# 780-00012-P4_rev4_Sch_M2_Focus_Drive.net
KiCad netlist of a schematic drawn in Altium Designer
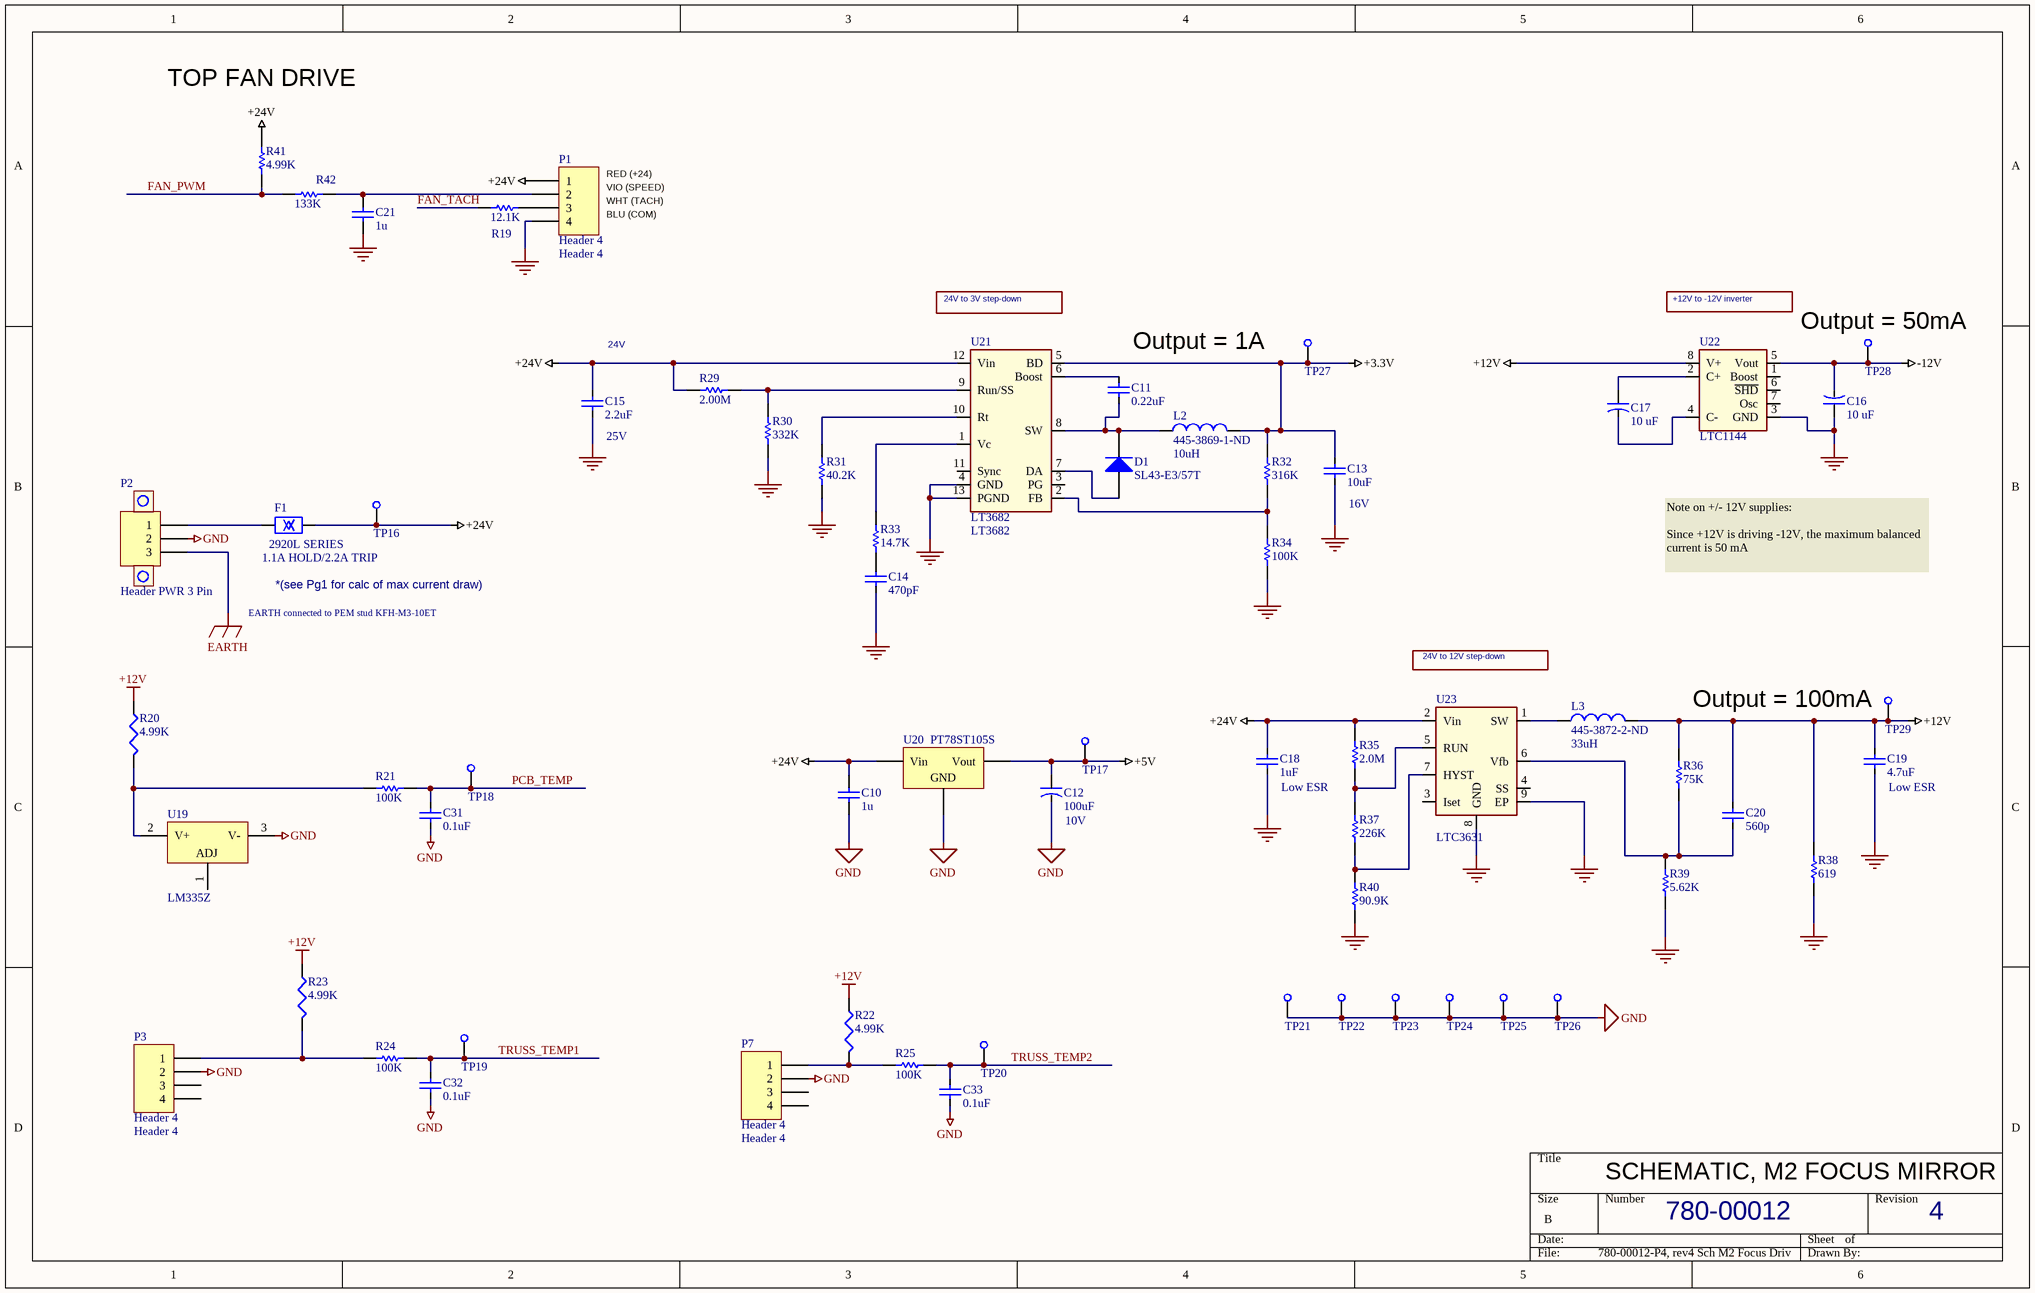
[diagram p0: 780-00012-P4, rev4 Sch M2 Focus Drive.SchDoc]

(export (version "E")
  (design (tool "Eeschema 10.0.6"))
  (components
    (comp (ref "C10")
      (value "1u")
      (footprint "2012[0805]")
      (description "Capacitor")
      (fields (field (name "MANUFACTURER") "Taiyo Yuden"))
      (libsource (lib "Miscellaneous Devices") (part "Cap"))
    )
    (comp (ref "C11")
      (value "0.22uF")
      (footprint "SMD_0805")
      (description "Capacitor")
      (fields (field (name "Comment") "Cap SMD"))
      (libsource (lib "Richs Schematic Components") (part "Cap SMD"))
    )
    (comp (ref "C12")
      (value "10V")
      (footprint "SMD_CAP_7343")
      (description "outline 6.0mm x 3.2mm")
      (fields (field (name "MANUFACTURER") "kEMET") (field (name "ALTIUM_VALUE") "100uF"))
      (libsource (lib "Richs Schematic Components") (part "Cap Tant 35V"))
    )
    (comp (ref "C13")
      (value "16V")
      (footprint "SMD_0805")
      (description "Capacitor")
      (fields (field (name "ALTIUM_VALUE") "10uF"))
      (libsource (lib "Richs Schematic Components") (part "Cap SMD"))
    )
    (comp (ref "C14")
      (value "470pF")
      (footprint "SMD_0805")
      (description "Capacitor")
      (fields (field (name "Comment") "Cap SMD"))
      (libsource (lib "Richs Schematic Components") (part "Cap SMD"))
    )
    (comp (ref "C15")
      (value "25V")
      (footprint "SMD_0805")
      (description "Capacitor")
      (fields (field (name "MANUFACTURER") "Taiyo Yuden") (field (name "ALTIUM_VALUE") "2.2uF"))
      (libsource (lib "Richs Schematic Components") (part "Cap SMD"))
    )
    (comp (ref "C16")
      (value "10 uF")
      (footprint "SMD_CAP_3216")
      (description "outline 3.2mm x 1.6mm")
      (fields (field (name "MANUFACTURER") "KEMET") (field (name "Comment") "16V"))
      (libsource (lib "Richs Schematic Components") (part "Cap Tant 16V"))
    )
    (comp (ref "C17")
      (value "10 uF")
      (footprint "SMD_CAP_3216")
      (description "outline 3.2mm x 1.6mm")
      (fields (field (name "MANUFACTURER") "KEMET") (field (name "Comment") "16V"))
      (libsource (lib "Richs Schematic Components") (part "Cap Tant 16V"))
    )
    (comp (ref "C18")
      (value "Low ESR")
      (footprint "SMD_1206")
      (description "Capacitor")
      (fields (field (name "MANUFACTURER") "TDK") (field (name "ALTIUM_VALUE") "1uF"))
      (libsource (lib "Richs Schematic Components") (part "Cap SMD"))
    )
    (comp (ref "C19")
      (value "Low ESR")
      (footprint "SMD_1206")
      (description "Capacitor")
      (fields (field (name "MANUFACTURER") "TDK") (field (name "ALTIUM_VALUE") "4.7uF"))
      (libsource (lib "Richs Schematic Components") (part "Cap SMD"))
    )
    (comp (ref "C20")
      (value "560p")
      (footprint "SMD_0805")
      (description "Capacitor")
      (fields (field (name "Comment") "Cap SMD"))
      (libsource (lib "Richs Schematic Components") (part "Cap SMD"))
    )
    (comp (ref "C21")
      (value "1u")
      (footprint "2012[0805]")
      (description "Capacitor")
      (fields (field (name "MANUFACTURER") "Taiyo Yuden"))
      (libsource (lib "Miscellaneous Devices") (part "Cap"))
    )
    (comp (ref "C31")
      (value "0.1uF")
      (footprint "SMD_0805")
      (description "Capacitor")
      (fields (field (name "MANUFACTURER") "AVX") (field (name "Comment") "Cap SMD"))
      (libsource (lib "Richs Schematic Components") (part "Cap SMD"))
    )
    (comp (ref "C32")
      (value "0.1uF")
      (footprint "SMD_0805")
      (description "Capacitor")
      (fields (field (name "MANUFACTURER") "AVX") (field (name "Comment") "Cap SMD"))
      (libsource (lib "Richs Schematic Components") (part "Cap SMD"))
    )
    (comp (ref "C33")
      (value "0.1uF")
      (footprint "SMD_0805")
      (description "Capacitor")
      (fields (field (name "MANUFACTURER") "AVX") (field (name "Comment") "Cap SMD"))
      (libsource (lib "Richs Schematic Components") (part "Cap SMD"))
    )
    (comp (ref "D1")
      (value "SL43-E3/57T")
      (footprint "DO-214AB")
      (description "Default Diode")
      (fields (field (name "MANUFACTURER") "Vishay/Dale"))
      (libsource (lib "Miscellaneous Devices") (part "Diode"))
    )
    (comp (ref "F1")
      (value "2920L SERIES")
      (footprint "SMD 2920  PolySwitch")
      (description "Polyswitch")
      (fields (field (name "ALTIUM_VALUE") "1.1A HOLD/2.2A TRIP"))
      (libsource (lib "Richs Schematic Components") (part "Fuse Resettable"))
    )
    (comp (ref "L2")
      (value "445-3869-1-ND")
      (footprint "Inductor TDC SLF")
      (description "Inductor")
      (fields (field (name "MANUFACTURER") "TDK") (field (name "ALTIUM_VALUE") "10uH"))
      (libsource (lib "Richs Schematic Components") (part "Inductor SMD 10uH 1.8A"))
    )
    (comp (ref "L3")
      (value "445-3872-2-ND")
      (footprint "Inductor TDC SLF")
      (description "Inductor")
      (fields (field (name "MANUFACTURER") "TDK") (field (name "ALTIUM_VALUE") "33uH"))
      (libsource (lib "Richs Schematic Components") (part "Inductor SMD 10uH 1.8A"))
    )
    (comp (ref "P1")
      (value "Header 4")
      (footprint "HDR1X4 for IDC")
      (description "Header, 4-Pin")
      (fields (field (name "ALTIUM_VALUE") "Header 4"))
      (libsource (lib "") (part "Header 4_1"))
    )
    (comp (ref "P2")
      (value "Header PWR 3 Pin")
      (footprint "HDR-3 pin w/screw")
      (description "Header, 3-Pin")
      (fields (field (name "MANUFACTURER") "Tyco"))
      (libsource (lib "Richs Schematic Components") (part "Header 3 PWR"))
    )
    (comp (ref "P3")
      (value "Header 4")
      (footprint "HDR1X4 for IDC")
      (description "Header, 4-Pin")
      (fields (field (name "ALTIUM_VALUE") "Header 4"))
      (libsource (lib "Richs Schematic Components") (part "Header 4"))
    )
    (comp (ref "P7")
      (value "Header 4")
      (footprint "HDR1X4 for IDC")
      (description "Header, 4-Pin")
      (fields (field (name "ALTIUM_VALUE") "Header 4"))
      (libsource (lib "Richs Schematic Components") (part "Header 4"))
    )
    (comp (ref "R19")
      (value "12.1K")
      (footprint "SMD_0805")
      (description "Resistor 0805")
      (fields (field (name "MANUFACTURER") "Vishay/Dale") (field (name "Comment") "Res 0805"))
      (libsource (lib "Richs Schematic Components") (part "Res SMD"))
    )
    (comp (ref "R20")
      (value "4.99K")
      (footprint "smd_0805")
      (description "Resistor")
      (fields (field (name "MANUFACTURER") "DALE") (field (name "Comment") "Res3"))
      (libsource (lib "Miscellaneous Devices") (part "Res3"))
    )
    (comp (ref "R21")
      (value "100K")
      (footprint "SMD_0805")
      (description "Resistor")
      (fields (field (name "MANUFACTURER") "Vishay/Dale") (field (name "Comment") "Res SMD"))
      (libsource (lib "Richs Schematic Components") (part "Res SMD"))
    )
    (comp (ref "R22")
      (value "4.99K")
      (footprint "smd_0805")
      (description "Resistor")
      (fields (field (name "MANUFACTURER") "DALE") (field (name "Comment") "Res3"))
      (libsource (lib "Miscellaneous Devices") (part "Res3"))
    )
    (comp (ref "R23")
      (value "4.99K")
      (footprint "smd_0805")
      (description "Resistor")
      (fields (field (name "MANUFACTURER") "DALE") (field (name "Comment") "Res3"))
      (libsource (lib "Miscellaneous Devices") (part "Res3"))
    )
    (comp (ref "R24")
      (value "100K")
      (footprint "SMD_0805")
      (description "Resistor")
      (fields (field (name "MANUFACTURER") "Vishay/Dale") (field (name "Comment") "Res SMD"))
      (libsource (lib "Richs Schematic Components") (part "Res SMD"))
    )
    (comp (ref "R25")
      (value "100K")
      (footprint "SMD_0805")
      (description "Resistor")
      (fields (field (name "MANUFACTURER") "Vishay/Dale") (field (name "Comment") "Res SMD"))
      (libsource (lib "Richs Schematic Components") (part "Res SMD"))
    )
    (comp (ref "R29")
      (value "2.00M")
      (footprint "SMD_0805")
      (description "Resistor 0805")
      (fields (field (name "MANUFACTURER") "Vishay/Dale") (field (name "Comment") "Res 0805"))
      (libsource (lib "Richs Schematic Components") (part "Res SMD"))
    )
    (comp (ref "R30")
      (value "332K")
      (footprint "SMD_0805")
      (description "Resistor 0805")
      (fields (field (name "MANUFACTURER") "Vishay/Dale") (field (name "Comment") "Res 0805"))
      (libsource (lib "Richs Schematic Components") (part "Res SMD"))
    )
    (comp (ref "R31")
      (value "40.2K")
      (footprint "SMD_0805")
      (description "Resistor 0805")
      (fields (field (name "MANUFACTURER") "Vishay/Dale") (field (name "Comment") "Res 0805"))
      (libsource (lib "Richs Schematic Components") (part "Res SMD"))
    )
    (comp (ref "R32")
      (value "316K")
      (footprint "SMD_0805")
      (description "Resistor 0805")
      (fields (field (name "MANUFACTURER") "Vishay/Dale") (field (name "Comment") "Res 0805"))
      (libsource (lib "Richs Schematic Components") (part "Res SMD"))
    )
    (comp (ref "R33")
      (value "14.7K")
      (footprint "SMD_0805")
      (description "Resistor 0805")
      (fields (field (name "MANUFACTURER") "Vishay/Dale") (field (name "Comment") "Res 0805"))
      (libsource (lib "Richs Schematic Components") (part "Res SMD"))
    )
    (comp (ref "R34")
      (value "100K")
      (footprint "SMD_0805")
      (description "Resistor 0805")
      (fields (field (name "MANUFACTURER") "Vishay/Dale") (field (name "Comment") "Res 0805"))
      (libsource (lib "Richs Schematic Components") (part "Res SMD"))
    )
    (comp (ref "R35")
      (value "2.0M")
      (footprint "SMD_0805")
      (description "Resistor 0805")
      (fields (field (name "MANUFACTURER") "Vishay/Dale") (field (name "Comment") "Res 0805"))
      (libsource (lib "Richs Schematic Components") (part "Res SMD"))
    )
    (comp (ref "R36")
      (value "75K")
      (footprint "SMD_0805")
      (description "Resistor 0805")
      (fields (field (name "MANUFACTURER") "Vishay/Dale") (field (name "Comment") "Res 0805"))
      (libsource (lib "Richs Schematic Components") (part "Res SMD"))
    )
    (comp (ref "R37")
      (value "226K")
      (footprint "SMD_0805")
      (description "Resistor 0805")
      (fields (field (name "MANUFACTURER") "Vishay/Dale") (field (name "Comment") "Res 0805"))
      (libsource (lib "Richs Schematic Components") (part "Res SMD"))
    )
    (comp (ref "R38")
      (value "619")
      (footprint "SMD_0805")
      (description "Resistor 0805")
      (fields (field (name "MANUFACTURER") "Vishay/Dale") (field (name "Comment") "Res 0805"))
      (libsource (lib "Richs Schematic Components") (part "Res SMD"))
    )
    (comp (ref "R39")
      (value "5.62K")
      (footprint "SMD_0805")
      (description "Resistor 0805")
      (fields (field (name "MANUFACTURER") "Vishay/Dale") (field (name "Comment") "Res 0805"))
      (libsource (lib "Richs Schematic Components") (part "Res SMD"))
    )
    (comp (ref "R40")
      (value "90.9K")
      (footprint "SMD_0805")
      (description "Resistor 0805")
      (fields (field (name "MANUFACTURER") "Vishay/Dale") (field (name "Comment") "Res 0805"))
      (libsource (lib "Richs Schematic Components") (part "Res SMD"))
    )
    (comp (ref "R41")
      (value "4.99K")
      (footprint "SMD_0805")
      (description "Resistor 0805")
      (fields (field (name "MANUFACTURER") "Vishay/Dale") (field (name "Comment") "Res 0805"))
      (libsource (lib "Richs Schematic Components") (part "Res SMD"))
    )
    (comp (ref "R42")
      (value "133K")
      (footprint "SMD_0805")
      (description "Resistor 0805")
      (fields (field (name "MANUFACTURER") "Vishay/Dale") (field (name "Comment") "Res 0805"))
      (libsource (lib "Richs Schematic Components") (part "Res SMD"))
    )
    (comp (ref "TP16")
      (value "Test Point SMD")
      (footprint "SMD_TEST POINT")
      (description "SMD loop test point")
      (libsource (lib "Richs Schematic Components") (part "Test Point SMD"))
    )
    (comp (ref "TP17")
      (value "Test Point SMD")
      (footprint "SMD_TEST POINT")
      (description "SMD loop test point")
      (libsource (lib "Richs Schematic Components") (part "Test Point SMD"))
    )
    (comp (ref "TP18")
      (value "Test Point SMD")
      (footprint "SMD_TEST POINT")
      (description "SMD loop test point")
      (libsource (lib "Richs Schematic Components") (part "Test Point SMD"))
    )
    (comp (ref "TP19")
      (value "Test Point SMD")
      (footprint "SMD_TEST POINT")
      (description "SMD loop test point")
      (libsource (lib "Richs Schematic Components") (part "Test Point SMD"))
    )
    (comp (ref "TP20")
      (value "Test Point SMD")
      (footprint "SMD_TEST POINT")
      (description "SMD loop test point")
      (libsource (lib "Richs Schematic Components") (part "Test Point SMD"))
    )
    (comp (ref "TP21")
      (value "Test Point SMD")
      (footprint "SMD_TEST POINT")
      (description "SMD loop test point")
      (libsource (lib "Richs Schematic Components") (part "Test Point SMD"))
    )
    (comp (ref "TP22")
      (value "Test Point SMD")
      (footprint "SMD_TEST POINT")
      (description "SMD loop test point")
      (libsource (lib "Richs Schematic Components") (part "Test Point SMD"))
    )
    (comp (ref "TP23")
      (value "Test Point SMD")
      (footprint "SMD_TEST POINT")
      (description "SMD loop test point")
      (libsource (lib "Richs Schematic Components") (part "Test Point SMD"))
    )
    (comp (ref "TP24")
      (value "Test Point SMD")
      (footprint "SMD_TEST POINT")
      (description "SMD loop test point")
      (libsource (lib "Richs Schematic Components") (part "Test Point SMD"))
    )
    (comp (ref "TP25")
      (value "Test Point SMD")
      (footprint "SMD_TEST POINT")
      (description "SMD loop test point")
      (libsource (lib "Richs Schematic Components") (part "Test Point SMD"))
    )
    (comp (ref "TP26")
      (value "Test Point SMD")
      (footprint "SMD_TEST POINT")
      (description "SMD loop test point")
      (libsource (lib "Richs Schematic Components") (part "Test Point SMD"))
    )
    (comp (ref "TP27")
      (value "Test Point SMD")
      (footprint "SMD_TEST POINT")
      (description "SMD loop test point")
      (libsource (lib "Richs Schematic Components") (part "Test Point SMD"))
    )
    (comp (ref "TP28")
      (value "Test Point SMD")
      (footprint "SMD_TEST POINT")
      (description "SMD loop test point")
      (libsource (lib "Richs Schematic Components") (part "Test Point SMD"))
    )
    (comp (ref "TP29")
      (value "Test Point SMD")
      (footprint "SMD_TEST POINT")
      (description "SMD loop test point")
      (libsource (lib "Richs Schematic Components") (part "Test Point SMD"))
    )
    (comp (ref "U19")
      (value "LM335Z")
      (footprint "Z03A")
      (description "Precision Temperature Sensor")
      (fields (field (name "MANUFACTURER") "National Semiconductor"))
      (libsource (lib "NSC Temperature Sensor") (part "LM335Z"))
    )
    (comp (ref "U20")
      (value "PT78ST105S")
      (footprint "PSIP_3_SMD")
      (description "Voltage Regulator")
      (fields (field (name "MANUFACTURER") "Texas Instruments"))
      (libsource (lib "Miscellaneous Devices") (part "Volt Reg"))
    )
    (comp (ref "U21")
      (value "LT3682")
      (footprint "DD12/DFN12")
      (description "1A uPwr Step-Down switching regulator")
      (fields (field (name "MANUFACTURER") "Linear") (field (name "ALTIUM_VALUE") "LT3682"))
      (libsource (lib "Richs Schematic Components") (part "LT3682"))
    )
    (comp (ref "U22")
      (value "LTC1144")
      (footprint "S8_M")
      (description "IC VOLT CONV SW-CAP W/SHTDN8SOIC")
      (fields (field (name "MANUFACTURER") "Linear"))
      (libsource (lib "Richs Schematic Components") (part "LTC1144"))
    )
    (comp (ref "U23")
      (value "LTC3631")
      (footprint "DD8/DFN8")
      (description "IC CONV STP-DWN ADJ 8-DFN")
      (fields (field (name "MANUFACTURER") "Linear"))
      (libsource (lib "Richs Schematic Components") (part "LTC3631"))
    )
  )
  (nets
    (net (code "1") (name "+3.3V") (class "Default")
      (node (ref "C13") (pin "2") (pinfunction "2_2") (pintype "passive"))
      (node (ref "L2") (pin "2") (pinfunction "2_2") (pintype "passive"))
      (node (ref "R32") (pin "2") (pinfunction "2_2") (pintype "passive"))
      (node (ref "TP27") (pin "1") (pinfunction "TP_1") (pintype "passive"))
      (node (ref "U21") (pin "5") (pinfunction "BD_5") (pintype "passive"))
    )
    (net (code "2") (name "+5V") (class "Default")
      (node (ref "C12") (pin "pos") (pinfunction "1_pos") (pintype "passive"))
      (node (ref "TP17") (pin "1") (pinfunction "TP_1") (pintype "passive"))
      (node (ref "U20") (pin "3") (pinfunction "Vout_3") (pintype "passive"))
    )
    (net (code "3") (name "+12V") (class "Default")
      (node (ref "C19") (pin "2") (pinfunction "2_2") (pintype "passive"))
      (node (ref "C20") (pin "2") (pinfunction "2_2") (pintype "passive"))
      (node (ref "L3") (pin "2") (pinfunction "2_2") (pintype "passive"))
      (node (ref "R20") (pin "1") (pinfunction "1_1") (pintype "passive"))
      (node (ref "R22") (pin "1") (pinfunction "1_1") (pintype "passive"))
      (node (ref "R23") (pin "1") (pinfunction "1_1") (pintype "passive"))
      (node (ref "R36") (pin "2") (pinfunction "2_2") (pintype "passive"))
      (node (ref "R38") (pin "2") (pinfunction "2_2") (pintype "passive"))
      (node (ref "TP29") (pin "1") (pinfunction "TP_1") (pintype "passive"))
      (node (ref "U22") (pin "8") (pinfunction "V+_8") (pintype "power_in"))
    )
    (net (code "4") (name "+24V") (class "Default")
      (node (ref "C10") (pin "1") (pinfunction "1_1") (pintype "passive"))
      (node (ref "C15") (pin "2") (pinfunction "2_2") (pintype "passive"))
      (node (ref "C18") (pin "2") (pinfunction "2_2") (pintype "passive"))
      (node (ref "F1") (pin "2") (pinfunction "2_2") (pintype "passive"))
      (node (ref "P1") (pin "1") (pinfunction "1_1") (pintype "passive"))
      (node (ref "R29") (pin "1") (pinfunction "1_1") (pintype "passive"))
      (node (ref "R35") (pin "2") (pinfunction "2_2") (pintype "passive"))
      (node (ref "R41") (pin "2") (pinfunction "2_2") (pintype "passive"))
      (node (ref "TP16") (pin "1") (pinfunction "TP_1") (pintype "passive"))
      (node (ref "U20") (pin "1") (pinfunction "Vin_1") (pintype "passive"))
      (node (ref "U21") (pin "12") (pinfunction "Vin_12") (pintype "passive"))
      (node (ref "U23") (pin "2") (pinfunction "Vin_2") (pintype "passive"))
    )
    (net (code "5") (name "-12V") (class "Default")
      (node (ref "C16") (pin "2") (pinfunction "2_2") (pintype "passive"))
      (node (ref "TP28") (pin "1") (pinfunction "TP_1") (pintype "passive"))
      (node (ref "U22") (pin "5") (pinfunction "Vout_5") (pintype "passive"))
    )
    (net (code "6") (name "/FAN_PWM") (class "Default")
      (node (ref "R41") (pin "1") (pinfunction "1_1") (pintype "passive"))
      (node (ref "R42") (pin "1") (pinfunction "1_1") (pintype "passive"))
    )
    (net (code "7") (name "/FAN_TACH") (class "Default")
      (node (ref "R19") (pin "1") (pinfunction "1_1") (pintype "passive"))
    )
    (net (code "8") (name "/PCB_TEMP") (class "Default")
      (node (ref "C31") (pin "2") (pinfunction "2_2") (pintype "passive"))
      (node (ref "R21") (pin "1") (pinfunction "1_1") (pintype "passive"))
      (node (ref "TP18") (pin "1") (pinfunction "TP_1") (pintype "passive"))
    )
    (net (code "9") (name "/TRUSS_TEMP1") (class "Default")
      (node (ref "C32") (pin "2") (pinfunction "2_2") (pintype "passive"))
      (node (ref "R24") (pin "1") (pinfunction "1_1") (pintype "passive"))
      (node (ref "TP19") (pin "1") (pinfunction "TP_1") (pintype "passive"))
    )
    (net (code "10") (name "/TRUSS_TEMP2") (class "Default")
      (node (ref "C33") (pin "2") (pinfunction "2_2") (pintype "passive"))
      (node (ref "R25") (pin "1") (pinfunction "1_1") (pintype "passive"))
      (node (ref "TP20") (pin "1") (pinfunction "TP_1") (pintype "passive"))
    )
    (net (code "11") (name "EARTH") (class "Default")
      (node (ref "P2") (pin "3") (pinfunction "3_3") (pintype "passive"))
    )
    (net (code "12") (name "GND") (class "Default")
      (node (ref "C10") (pin "2") (pinfunction "2_2") (pintype "passive"))
      (node (ref "C12") (pin "neg") (pinfunction "2_neg") (pintype "passive"))
      (node (ref "C13") (pin "1") (pinfunction "1_1") (pintype "passive"))
      (node (ref "C14") (pin "1") (pinfunction "1_1") (pintype "passive"))
      (node (ref "C15") (pin "1") (pinfunction "1_1") (pintype "passive"))
      (node (ref "C16") (pin "1") (pinfunction "1_1") (pintype "passive"))
      (node (ref "C18") (pin "1") (pinfunction "1_1") (pintype "passive"))
      (node (ref "C19") (pin "1") (pinfunction "1_1") (pintype "passive"))
      (node (ref "C21") (pin "2") (pinfunction "2_2") (pintype "passive"))
      (node (ref "C31") (pin "1") (pinfunction "1_1") (pintype "passive"))
      (node (ref "C32") (pin "1") (pinfunction "1_1") (pintype "passive"))
      (node (ref "C33") (pin "1") (pinfunction "1_1") (pintype "passive"))
      (node (ref "P1") (pin "4") (pinfunction "4_4") (pintype "passive"))
      (node (ref "P2") (pin "2") (pinfunction "2_2") (pintype "passive"))
      (node (ref "P3") (pin "2") (pinfunction "2_2") (pintype "passive"))
      (node (ref "P7") (pin "2") (pinfunction "2_2") (pintype "passive"))
      (node (ref "R30") (pin "1") (pinfunction "1_1") (pintype "passive"))
      (node (ref "R31") (pin "1") (pinfunction "1_1") (pintype "passive"))
      (node (ref "R34") (pin "1") (pinfunction "1_1") (pintype "passive"))
      (node (ref "R38") (pin "1") (pinfunction "1_1") (pintype "passive"))
      (node (ref "R39") (pin "1") (pinfunction "1_1") (pintype "passive"))
      (node (ref "R40") (pin "1") (pinfunction "1_1") (pintype "passive"))
      (node (ref "TP21") (pin "1") (pinfunction "TP_1") (pintype "passive"))
      (node (ref "TP22") (pin "1") (pinfunction "TP_1") (pintype "passive"))
      (node (ref "TP23") (pin "1") (pinfunction "TP_1") (pintype "passive"))
      (node (ref "TP24") (pin "1") (pinfunction "TP_1") (pintype "passive"))
      (node (ref "TP25") (pin "1") (pinfunction "TP_1") (pintype "passive"))
      (node (ref "TP26") (pin "1") (pinfunction "TP_1") (pintype "passive"))
      (node (ref "U19") (pin "3") (pinfunction "V-_3") (pintype "passive"))
      (node (ref "U20") (pin "2") (pinfunction "GND_2") (pintype "passive"))
      (node (ref "U21") (pin "13") (pinfunction "PGND_13") (pintype "passive"))
      (node (ref "U21") (pin "4") (pinfunction "GND_4") (pintype "power_in"))
      (node (ref "U22") (pin "3") (pinfunction "GND_3") (pintype "passive"))
      (node (ref "U23") (pin "8") (pinfunction "GND_8") (pintype "passive"))
      (node (ref "U23") (pin "9") (pinfunction "EP_9") (pintype "passive"))
    )
    (net (code "13") (name "Net-(C14-Pad2)") (class "Default")
      (node (ref "C14") (pin "2") (pinfunction "2_2") (pintype "passive"))
      (node (ref "R33") (pin "1") (pinfunction "1_1") (pintype "passive"))
    )
    (net (code "14") (name "Net-(C21-Pad1)") (class "Default")
      (node (ref "C21") (pin "1") (pinfunction "1_1") (pintype "passive"))
      (node (ref "P1") (pin "2") (pinfunction "2_2") (pintype "passive"))
      (node (ref "R42") (pin "2") (pinfunction "2_2") (pintype "passive"))
    )
    (net (code "15") (name "Net-(D1-A)") (class "Default")
      (node (ref "D1") (pin "1") (pinfunction "A_1") (pintype "passive"))
      (node (ref "U21") (pin "7") (pinfunction "DA_7") (pintype "passive"))
    )
    (net (code "16") (name "Net-(D1-K)") (class "Default")
      (node (ref "C11") (pin "1") (pinfunction "1_1") (pintype "passive"))
      (node (ref "D1") (pin "2") (pinfunction "K_2") (pintype "passive"))
      (node (ref "L2") (pin "1") (pinfunction "1_1") (pintype "passive"))
      (node (ref "U21") (pin "8") (pinfunction "SW_8") (pintype "passive"))
    )
    (net (code "17") (name "Net-(F1-Pad1)") (class "Default")
      (node (ref "F1") (pin "1") (pinfunction "1_1") (pintype "passive"))
      (node (ref "P2") (pin "1") (pinfunction "1_1") (pintype "passive"))
    )
    (net (code "18") (name "Net-(P1-Pad3)") (class "Default")
      (node (ref "P1") (pin "3") (pinfunction "3_3") (pintype "passive"))
      (node (ref "R19") (pin "2") (pinfunction "2_2") (pintype "passive"))
    )
    (net (code "19") (name "Net-(P3-Pad1)") (class "Default")
      (node (ref "P3") (pin "1") (pinfunction "1_1") (pintype "passive"))
      (node (ref "R23") (pin "2") (pinfunction "2_2") (pintype "passive"))
      (node (ref "R24") (pin "2") (pinfunction "2_2") (pintype "passive"))
    )
    (net (code "20") (name "Net-(P7-Pad1)") (class "Default")
      (node (ref "P7") (pin "1") (pinfunction "1_1") (pintype "passive"))
      (node (ref "R22") (pin "2") (pinfunction "2_2") (pintype "passive"))
      (node (ref "R25") (pin "2") (pinfunction "2_2") (pintype "passive"))
    )
    (net (code "21") (name "Net-(U19-V+)") (class "Default")
      (node (ref "R20") (pin "2") (pinfunction "2_2") (pintype "passive"))
      (node (ref "R21") (pin "2") (pinfunction "2_2") (pintype "passive"))
      (node (ref "U19") (pin "2") (pinfunction "V+_2") (pintype "passive"))
    )
    (net (code "22") (name "Net-(U21-Boost)") (class "Default")
      (node (ref "C11") (pin "2") (pinfunction "2_2") (pintype "passive"))
      (node (ref "U21") (pin "6") (pinfunction "Boost_6") (pintype "passive"))
    )
    (net (code "23") (name "Net-(U21-FB)") (class "Default")
      (node (ref "R32") (pin "1") (pinfunction "1_1") (pintype "passive"))
      (node (ref "R34") (pin "2") (pinfunction "2_2") (pintype "passive"))
      (node (ref "U21") (pin "2") (pinfunction "FB_2") (pintype "passive"))
    )
    (net (code "24") (name "Net-(U21-Rt)") (class "Default")
      (node (ref "R31") (pin "2") (pinfunction "2_2") (pintype "passive"))
      (node (ref "U21") (pin "10") (pinfunction "Rt_10") (pintype "passive"))
    )
    (net (code "25") (name "Net-(U21-Run{slash}SS)") (class "Default")
      (node (ref "R29") (pin "2") (pinfunction "2_2") (pintype "passive"))
      (node (ref "R30") (pin "2") (pinfunction "2_2") (pintype "passive"))
      (node (ref "U21") (pin "9") (pinfunction "Run/SS_9") (pintype "passive"))
    )
    (net (code "26") (name "Net-(U21-Vc)") (class "Default")
      (node (ref "R33") (pin "2") (pinfunction "2_2") (pintype "passive"))
      (node (ref "U21") (pin "1") (pinfunction "Vc_1") (pintype "passive"))
    )
    (net (code "27") (name "Net-(U22-C+)") (class "Default")
      (node (ref "C17") (pin "1") (pinfunction "1_1") (pintype "passive"))
      (node (ref "U22") (pin "2") (pinfunction "C+_2") (pintype "passive"))
    )
    (net (code "28") (name "Net-(U22-C-)") (class "Default")
      (node (ref "C17") (pin "2") (pinfunction "2_2") (pintype "passive"))
      (node (ref "U22") (pin "4") (pinfunction "C-_4") (pintype "passive"))
    )
    (net (code "29") (name "Net-(U23-HYST)") (class "Default")
      (node (ref "R37") (pin "1") (pinfunction "1_1") (pintype "passive"))
      (node (ref "R40") (pin "2") (pinfunction "2_2") (pintype "passive"))
      (node (ref "U23") (pin "7") (pinfunction "HYST_7") (pintype "passive"))
    )
    (net (code "30") (name "Net-(U23-RUN)") (class "Default")
      (node (ref "R35") (pin "1") (pinfunction "1_1") (pintype "passive"))
      (node (ref "R37") (pin "2") (pinfunction "2_2") (pintype "passive"))
      (node (ref "U23") (pin "5") (pinfunction "RUN_5") (pintype "passive"))
    )
    (net (code "31") (name "Net-(U23-SW)") (class "Default")
      (node (ref "L3") (pin "1") (pinfunction "1_1") (pintype "passive"))
      (node (ref "U23") (pin "1") (pinfunction "SW_1") (pintype "passive"))
    )
    (net (code "32") (name "Net-(U23-Vfb)") (class "Default")
      (node (ref "C20") (pin "1") (pinfunction "1_1") (pintype "passive"))
      (node (ref "R36") (pin "1") (pinfunction "1_1") (pintype "passive"))
      (node (ref "R39") (pin "2") (pinfunction "2_2") (pintype "passive"))
      (node (ref "U23") (pin "6") (pinfunction "Vfb_6") (pintype "passive"))
    )
    (net (code "33") (name "SUPPORT") (class "Default")
      (node (ref "U20") (pin "0") (pinfunction "SUPPORT_0") (pintype "passive"))
    )
    (net (code "34") (name "unconnected-(P3-Pad3)") (class "Default")
      (node (ref "P3") (pin "3") (pinfunction "3_3") (pintype "passive"))
    )
    (net (code "35") (name "unconnected-(P3-Pad4)") (class "Default")
      (node (ref "P3") (pin "4") (pinfunction "4_4") (pintype "passive"))
    )
    (net (code "36") (name "unconnected-(P7-Pad3)") (class "Default")
      (node (ref "P7") (pin "3") (pinfunction "3_3") (pintype "passive"))
    )
    (net (code "37") (name "unconnected-(P7-Pad4)") (class "Default")
      (node (ref "P7") (pin "4") (pinfunction "4_4") (pintype "passive"))
    )
    (net (code "38") (name "unconnected-(U19-ADJ-Pad1)") (class "Default")
      (node (ref "U19") (pin "1") (pinfunction "ADJ_1") (pintype "passive"))
    )
    (net (code "39") (name "unconnected-(U21-PG-Pad3)") (class "Default")
      (node (ref "U21") (pin "3") (pinfunction "PG_3") (pintype "passive"))
    )
    (net (code "40") (name "unconnected-(U21-Sync-Pad11)") (class "Default")
      (node (ref "U21") (pin "11") (pinfunction "Sync_11") (pintype "passive"))
    )
    (net (code "41") (name "unconnected-(U22-Boost-Pad1)") (class "Default")
      (node (ref "U22") (pin "1") (pinfunction "Boost_1") (pintype "passive"))
    )
    (net (code "42") (name "unconnected-(U22-Osc-Pad7)") (class "Default")
      (node (ref "U22") (pin "7") (pinfunction "Osc_7") (pintype "passive"))
    )
    (net (code "43") (name "unconnected-(U22-~{SHD}-Pad6)") (class "Default")
      (node (ref "U22") (pin "6") (pinfunction "~{SHD}_6") (pintype "passive"))
    )
    (net (code "44") (name "unconnected-(U23-Iset-Pad3)") (class "Default")
      (node (ref "U23") (pin "3") (pinfunction "Iset_3") (pintype "passive"))
    )
    (net (code "45") (name "unconnected-(U23-SS-Pad4)") (class "Default")
      (node (ref "U23") (pin "4") (pinfunction "SS_4") (pintype "passive"))
    )
  )
)
